# RPI_3.net
KiCad netlist of a schematic drawn in Altium Designer
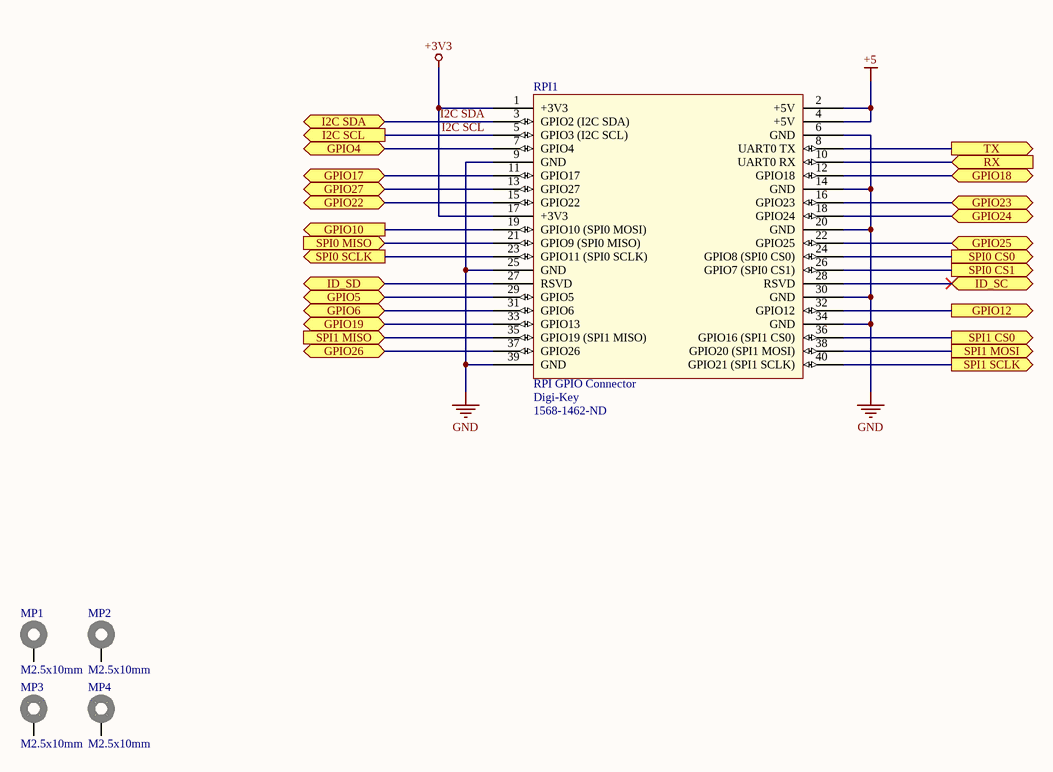
[diagram p0: RPI 3.SchDoc]

(export (version "E")
  (design (tool "Eeschema 10.0.6"))
  (components
    (comp (ref "MP1")
      (value "M2.5x10mm")
      (footprint "9774100151")
      (description "WA-SMSI SMT Steel Spacer, OD5.1mm, M2.5x10mm")
      (fields (field (name "PART NUMBER") "9774100151") (field (name "PUBLISHER") "Wurth Elektronik"))
      (libsource (lib "ALTIUM-SMSI_SMT_STEEL_SPACER_M3_THREAD_INTERNAL-rev19b") (part "9774100151"))
    )
    (comp (ref "MP2")
      (value "M2.5x10mm")
      (footprint "9774100151")
      (description "WA-SMSI SMT Steel Spacer, OD5.1mm, M2.5x10mm")
      (fields (field (name "PART NUMBER") "9774100151") (field (name "PUBLISHER") "Wurth Elektronik"))
      (libsource (lib "ALTIUM-SMSI_SMT_STEEL_SPACER_M3_THREAD_INTERNAL-rev19b") (part "9774100151"))
    )
    (comp (ref "MP3")
      (value "M2.5x10mm")
      (footprint "9774100151")
      (description "WA-SMSI SMT Steel Spacer, OD5.1mm, M2.5x10mm")
      (fields (field (name "PART NUMBER") "9774100151") (field (name "PUBLISHER") "Wurth Elektronik"))
      (libsource (lib "ALTIUM-SMSI_SMT_STEEL_SPACER_M3_THREAD_INTERNAL-rev19b") (part "9774100151"))
    )
    (comp (ref "MP4")
      (value "M2.5x10mm")
      (footprint "9774100151")
      (description "WA-SMSI SMT Steel Spacer, OD5.1mm, M2.5x10mm")
      (fields (field (name "PART NUMBER") "9774100151") (field (name "PUBLISHER") "Wurth Elektronik"))
      (libsource (lib "ALTIUM-SMSI_SMT_STEEL_SPACER_M3_THREAD_INTERNAL-rev19b") (part "9774100151"))
    )
    (comp (ref "RPI1")
      (value "RPI GPIO Connector")
      (footprint "rpi")
      (description "GPIO Header for Raspberry Pi A+/B+/Pi 2/Pi 3 - 2x20")
      (fields
        (field (name "MANUFACTURER") "SparkFun Electronics")
        (field (name "MANUFACTURER PART NUMBER") "PRT-14017")
        (field (name "SUPPLIER 1") "Digi-Key")
        (field (name "SUPPLIER PART NUMBER 1") "1568-1462-ND")
      )
      (libsource (lib "rpi") (part "rpi connector"))
    )
  )
  (nets
    (net (code "1") (name "+3V3") (class "Default")
      (node (ref "RPI1") (pin "1") (pinfunction "+3V3_1") (pintype "power_in"))
      (node (ref "RPI1") (pin "17") (pinfunction "+3V3_17") (pintype "power_in"))
    )
    (net (code "2") (name "+5") (class "Default")
      (node (ref "RPI1") (pin "2") (pinfunction "+5V_2") (pintype "power_in"))
      (node (ref "RPI1") (pin "4") (pinfunction "+5V_4") (pintype "power_in"))
    )
    (net (code "3") (name "/GPIO4") (class "Default")
      (node (ref "RPI1") (pin "7") (pinfunction "GPIO4_7") (pintype "bidirectional"))
    )
    (net (code "4") (name "/GPIO5") (class "Default")
      (node (ref "RPI1") (pin "29") (pinfunction "GPIO5_29") (pintype "bidirectional"))
    )
    (net (code "5") (name "/GPIO6") (class "Default")
      (node (ref "RPI1") (pin "31") (pinfunction "GPIO6_31") (pintype "bidirectional"))
    )
    (net (code "6") (name "/GPIO10") (class "Default")
      (node (ref "RPI1") (pin "19") (pinfunction "GPIO10_(SPI0_MOSI)_19") (pintype "bidirectional"))
    )
    (net (code "7") (name "/GPIO12") (class "Default")
      (node (ref "RPI1") (pin "32") (pinfunction "GPIO12_32") (pintype "bidirectional"))
    )
    (net (code "8") (name "/GPIO17") (class "Default")
      (node (ref "RPI1") (pin "11") (pinfunction "GPIO17_11") (pintype "bidirectional"))
    )
    (net (code "9") (name "/GPIO18") (class "Default")
      (node (ref "RPI1") (pin "12") (pinfunction "GPIO18_12") (pintype "bidirectional"))
    )
    (net (code "10") (name "/GPIO19") (class "Default")
      (node (ref "RPI1") (pin "33") (pinfunction "GPIO13_33") (pintype "bidirectional"))
    )
    (net (code "11") (name "/GPIO22") (class "Default")
      (node (ref "RPI1") (pin "15") (pinfunction "GPIO22_15") (pintype "bidirectional"))
    )
    (net (code "12") (name "/GPIO23") (class "Default")
      (node (ref "RPI1") (pin "16") (pinfunction "GPIO23_16") (pintype "bidirectional"))
    )
    (net (code "13") (name "/GPIO24") (class "Default")
      (node (ref "RPI1") (pin "18") (pinfunction "GPIO24_18") (pintype "bidirectional"))
    )
    (net (code "14") (name "/GPIO25") (class "Default")
      (node (ref "RPI1") (pin "22") (pinfunction "GPIO25_22") (pintype "bidirectional"))
    )
    (net (code "15") (name "/GPIO26") (class "Default")
      (node (ref "RPI1") (pin "37") (pinfunction "GPIO26_37") (pintype "bidirectional"))
    )
    (net (code "16") (name "/GPIO27") (class "Default")
      (node (ref "RPI1") (pin "13") (pinfunction "GPIO27_13") (pintype "bidirectional"))
    )
    (net (code "17") (name "/I2C SCL") (class "Default")
      (node (ref "RPI1") (pin "5") (pinfunction "GPIO3_(I2C_SCL)_5") (pintype "bidirectional"))
    )
    (net (code "18") (name "/I2C SDA") (class "Default")
      (node (ref "RPI1") (pin "3") (pinfunction "GPIO2_(I2C_SDA)_3") (pintype "bidirectional"))
    )
    (net (code "19") (name "/ID_SC") (class "Default")
      (node (ref "RPI1") (pin "28") (pinfunction "RSVD_28") (pintype "passive+no_connect"))
    )
    (net (code "20") (name "/ID_SD") (class "Default")
      (node (ref "RPI1") (pin "27") (pinfunction "RSVD_27") (pintype "passive"))
    )
    (net (code "21") (name "/RX") (class "Default")
      (node (ref "RPI1") (pin "10") (pinfunction "UART0_RX_10") (pintype "bidirectional"))
    )
    (net (code "22") (name "/SPI0 CS0") (class "Default")
      (node (ref "RPI1") (pin "24") (pinfunction "GPIO8_(SPI0_CS0)_24") (pintype "bidirectional"))
    )
    (net (code "23") (name "/SPI0 CS1") (class "Default")
      (node (ref "RPI1") (pin "26") (pinfunction "GPIO7_(SPI0_CS1)_26") (pintype "bidirectional"))
    )
    (net (code "24") (name "/SPI0 MISO") (class "Default")
      (node (ref "RPI1") (pin "21") (pinfunction "GPIO9_(SPI0_MISO)_21") (pintype "bidirectional"))
    )
    (net (code "25") (name "/SPI0 SCLK") (class "Default")
      (node (ref "RPI1") (pin "23") (pinfunction "GPIO11_(SPI0_SCLK)_23") (pintype "bidirectional"))
    )
    (net (code "26") (name "/SPI1 CS0") (class "Default")
      (node (ref "RPI1") (pin "36") (pinfunction "GPIO16_(SPI1_CS0)_36") (pintype "bidirectional"))
    )
    (net (code "27") (name "/SPI1 MISO") (class "Default")
      (node (ref "RPI1") (pin "35") (pinfunction "GPIO19_(SPI1_MISO)_35") (pintype "bidirectional"))
    )
    (net (code "28") (name "/SPI1 MOSI") (class "Default")
      (node (ref "RPI1") (pin "38") (pinfunction "GPIO20_(SPI1_MOSI)_38") (pintype "bidirectional"))
    )
    (net (code "29") (name "/SPI1 SCLK") (class "Default")
      (node (ref "RPI1") (pin "40") (pinfunction "GPIO21_(SPI1_SCLK)_40") (pintype "bidirectional"))
    )
    (net (code "30") (name "/TX") (class "Default")
      (node (ref "RPI1") (pin "8") (pinfunction "UART0_TX_8") (pintype "bidirectional"))
    )
    (net (code "31") (name "GND") (class "Default")
      (node (ref "RPI1") (pin "14") (pinfunction "GND_14") (pintype "power_in"))
      (node (ref "RPI1") (pin "20") (pinfunction "GND_20") (pintype "power_in"))
      (node (ref "RPI1") (pin "25") (pinfunction "GND_25") (pintype "power_in"))
      (node (ref "RPI1") (pin "30") (pinfunction "GND_30") (pintype "power_in"))
      (node (ref "RPI1") (pin "34") (pinfunction "GND_34") (pintype "passive"))
      (node (ref "RPI1") (pin "39") (pinfunction "GND_39") (pintype "power_in"))
      (node (ref "RPI1") (pin "6") (pinfunction "GND_6") (pintype "power_in"))
      (node (ref "RPI1") (pin "9") (pinfunction "GND_9") (pintype "power_in"))
    )
    (net (code "32") (name "unconnected-(MP1-Pad1)") (class "Default")
      (node (ref "MP1") (pin "1") (pinfunction "1_1") (pintype "passive"))
    )
    (net (code "33") (name "unconnected-(MP2-Pad1)") (class "Default")
      (node (ref "MP2") (pin "1") (pinfunction "1_1") (pintype "passive"))
    )
    (net (code "34") (name "unconnected-(MP3-Pad1)") (class "Default")
      (node (ref "MP3") (pin "1") (pinfunction "1_1") (pintype "passive"))
    )
    (net (code "35") (name "unconnected-(MP4-Pad1)") (class "Default")
      (node (ref "MP4") (pin "1") (pinfunction "1_1") (pintype "passive"))
    )
  )
)
